# or.net
KiCad netlist of a schematic drawn in EAGLE
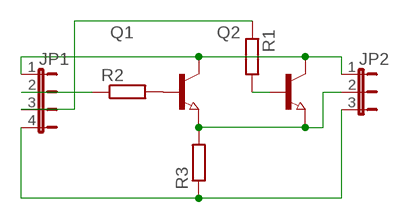
[diagram p0: schematic, sheet 1]

(export (version "E")
  (design (tool "Eeschema 10.0.6"))
  (components
    (comp (ref "JP1")
      (value "JP4E")
      (footprint "eagle-import:JP4")
      (libsource (lib "eagle-import") (part "JP4E"))
    )
    (comp (ref "JP2")
      (value "JP2W")
      (footprint "eagle-import:JP2W")
      (libsource (lib "eagle-import") (part "JP2W"))
    )
    (comp (ref "Q1")
      (value "NPN-TRANSISTOR_SOT23")
      (footprint "eagle-import:SOT23")
      (libsource (lib "eagle-import") (part "NPN-TRANSISTOR_SOT23"))
    )
    (comp (ref "Q2")
      (value "NPN-TRANSISTOR_SOT23")
      (footprint "eagle-import:SOT23")
      (libsource (lib "eagle-import") (part "NPN-TRANSISTOR_SOT23"))
    )
    (comp (ref "R1")
      (value "R-EU_R1206")
      (footprint "eagle-import:R1206")
      (libsource (lib "eagle-import") (part "R-EU_R1206"))
    )
    (comp (ref "R2")
      (value "R-EU_R1206")
      (footprint "eagle-import:R1206")
      (libsource (lib "eagle-import") (part "R-EU_R1206"))
    )
    (comp (ref "R3")
      (value "R-EU_R1206")
      (footprint "eagle-import:R1206")
      (libsource (lib "eagle-import") (part "R-EU_R1206"))
    )
  )
  (nets
    (net (code "1") (name "Net-(JP1-Pad2)") (class "Default")
      (node (ref "JP1") (pin "2") (pinfunction "2_2") (pintype "passive"))
      (node (ref "R2") (pin "1") (pinfunction "1_1") (pintype "passive"))
    )
    (net (code "2") (name "Net-(JP1-Pad3)") (class "Default")
      (node (ref "JP1") (pin "3") (pinfunction "3_3") (pintype "passive"))
      (node (ref "R1") (pin "1") (pinfunction "1_1") (pintype "passive"))
    )
    (net (code "3") (name "Net-(JP1-Pad4)") (class "Default")
      (node (ref "JP1") (pin "4") (pinfunction "4_4") (pintype "passive"))
      (node (ref "JP2") (pin "3") (pinfunction "3_3") (pintype "passive"))
      (node (ref "R3") (pin "1") (pinfunction "1_1") (pintype "passive"))
    )
    (net (code "4") (name "Net-(Q1-B)") (class "Default")
      (node (ref "Q1") (pin "1") (pinfunction "B_1") (pintype "passive"))
      (node (ref "R2") (pin "2") (pinfunction "2_2") (pintype "passive"))
    )
    (net (code "5") (name "Net-(Q1-C)") (class "Default")
      (node (ref "JP1") (pin "1") (pinfunction "1_1") (pintype "passive"))
      (node (ref "JP2") (pin "1") (pinfunction "1_1") (pintype "passive"))
      (node (ref "Q1") (pin "3") (pinfunction "C_3") (pintype "passive"))
      (node (ref "Q2") (pin "3") (pinfunction "C_3") (pintype "passive"))
    )
    (net (code "6") (name "Net-(Q1-E)") (class "Default")
      (node (ref "JP2") (pin "2") (pinfunction "2_2") (pintype "passive"))
      (node (ref "Q1") (pin "2") (pinfunction "E_2") (pintype "passive"))
      (node (ref "Q2") (pin "2") (pinfunction "E_2") (pintype "passive"))
      (node (ref "R3") (pin "2") (pinfunction "2_2") (pintype "passive"))
    )
    (net (code "7") (name "Net-(Q2-B)") (class "Default")
      (node (ref "Q2") (pin "1") (pinfunction "B_1") (pintype "passive"))
      (node (ref "R1") (pin "2") (pinfunction "2_2") (pintype "passive"))
    )
  )
)
